# comparator-denary-buffer.net
KiCad netlist of a schematic drawn in EAGLE
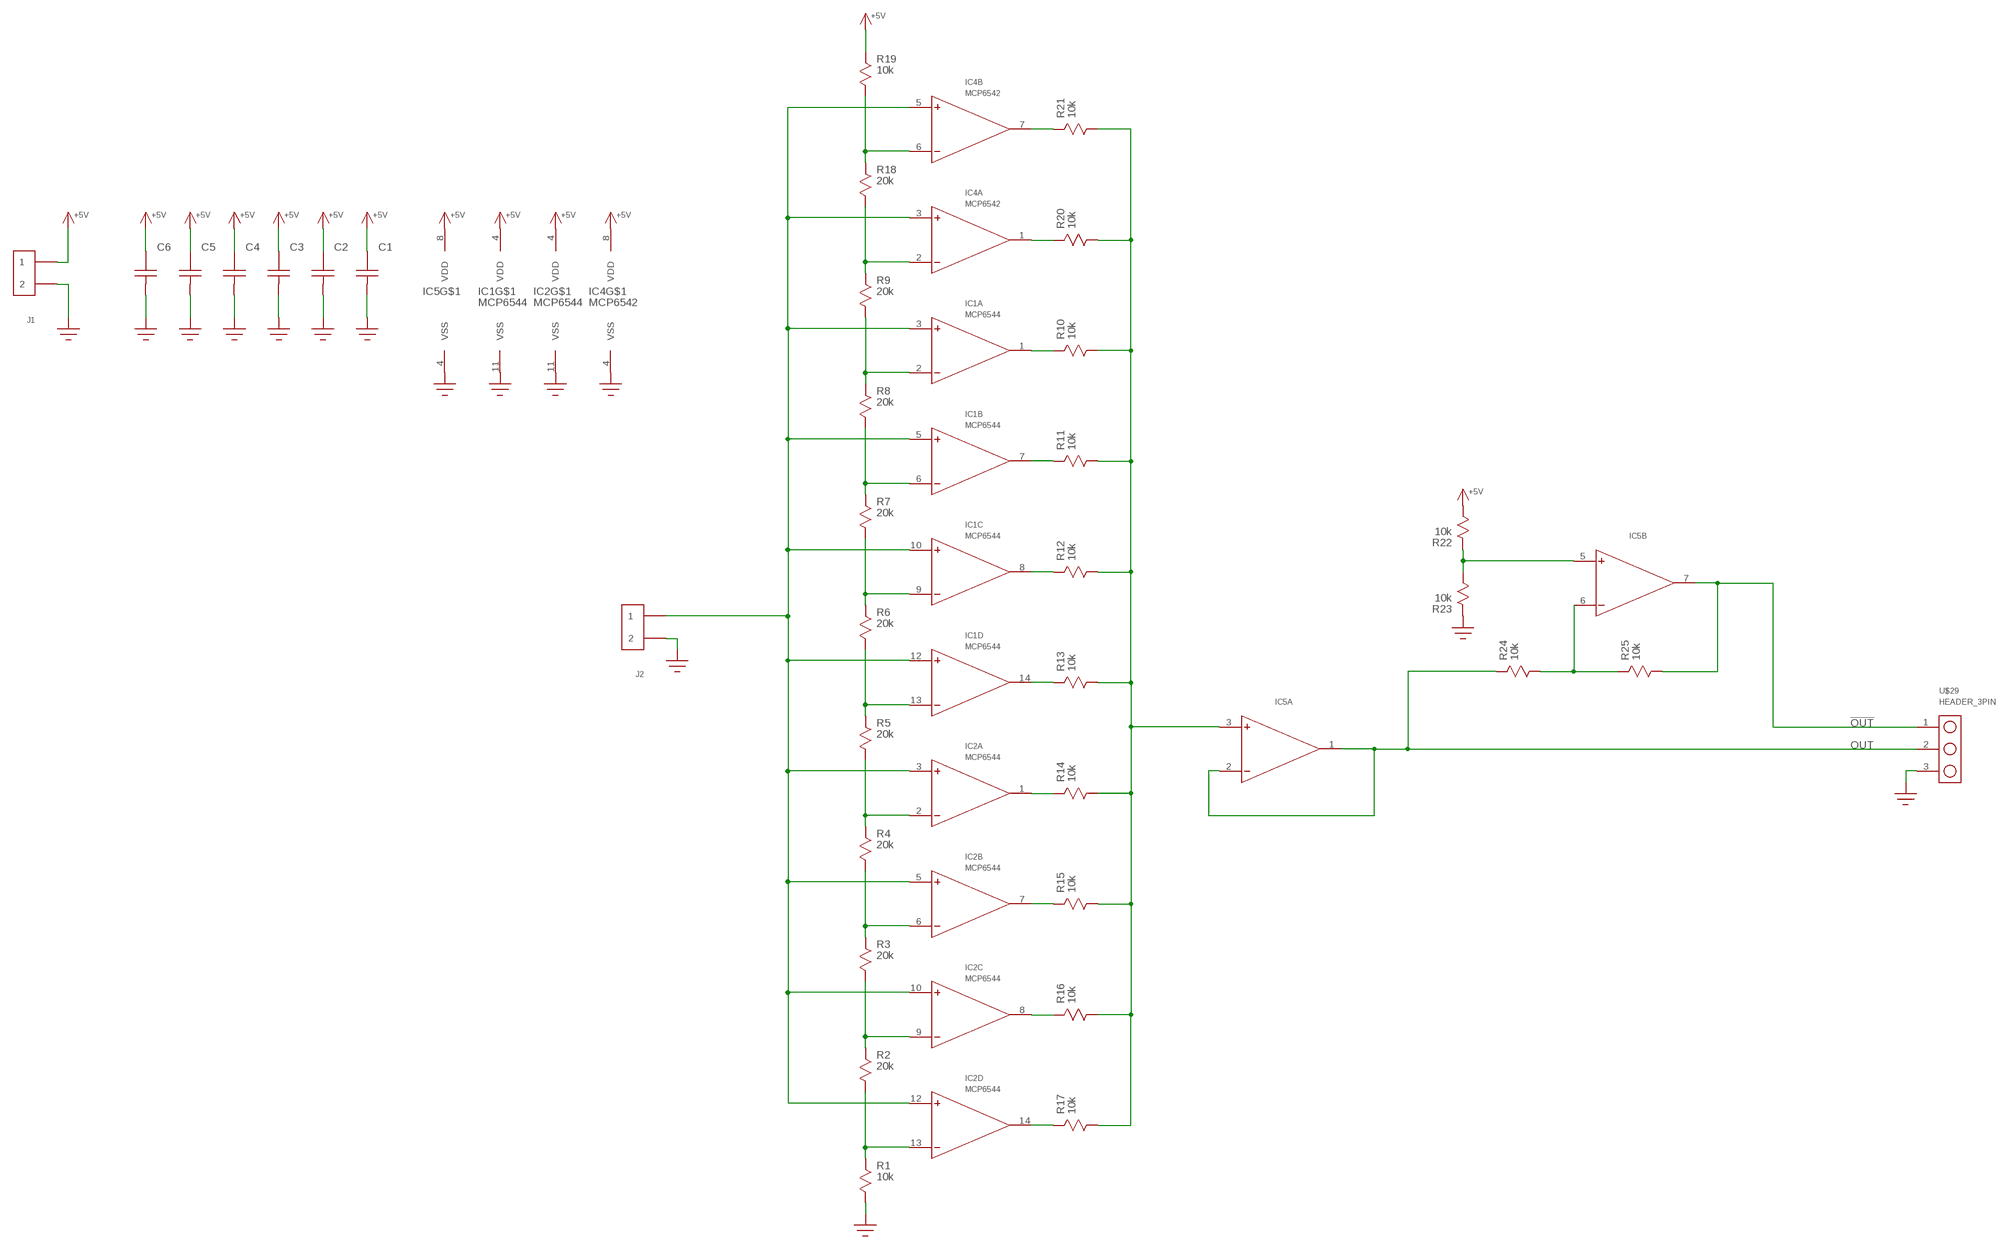
[diagram p0: schematic, sheet 1]

(export (version "E")
  (design (tool "Eeschema 10.0.6"))
  (components
    (comp (ref "C1")
      (value "C0603")
      (footprint "eagle-import:C0603")
      (libsource (lib "eagle-import") (part "C0603"))
    )
    (comp (ref "C2")
      (value "C0603")
      (footprint "eagle-import:C0603")
      (libsource (lib "eagle-import") (part "C0603"))
    )
    (comp (ref "C3")
      (value "C0603")
      (footprint "eagle-import:C0603")
      (libsource (lib "eagle-import") (part "C0603"))
    )
    (comp (ref "C4")
      (value "C0603")
      (footprint "eagle-import:C0603")
      (libsource (lib "eagle-import") (part "C0603"))
    )
    (comp (ref "C5")
      (value "C0603")
      (footprint "eagle-import:C0603")
      (libsource (lib "eagle-import") (part "C0603"))
    )
    (comp (ref "C6")
      (value "C1206")
      (footprint "eagle-import:1206")
      (libsource (lib "eagle-import") (part "C1206"))
    )
    (comp (ref "IC1")
      (value "MCP6544")
      (footprint "eagle-import:SOIC-14")
      (libsource (lib "eagle-import") (part "MCP6544SOIC"))
    )
    (comp (ref "IC2")
      (value "MCP6544")
      (footprint "eagle-import:SOIC-14")
      (libsource (lib "eagle-import") (part "MCP6544SOIC"))
    )
    (comp (ref "IC4")
      (value "MCP6542")
      (footprint "eagle-import:SOIC8")
      (libsource (lib "eagle-import") (part "MCP6542"))
    )
    (comp (ref "IC5")
      (value "MCP6L02")
      (footprint "eagle-import:SOIC8")
      (libsource (lib "eagle-import") (part "MCP6L02"))
    )
    (comp (ref "J1")
      (value "HEADER_2PIN")
      (footprint "eagle-import:HEADER_2PIN")
      (libsource (lib "eagle-import") (part "HEADER_2PIN"))
    )
    (comp (ref "J2")
      (value "HEADER_2PIN")
      (footprint "eagle-import:HEADER_2PIN")
      (libsource (lib "eagle-import") (part "HEADER_2PIN"))
    )
    (comp (ref "R1")
      (value "10k")
      (footprint "eagle-import:R0603")
      (libsource (lib "eagle-import") (part "R0603"))
    )
    (comp (ref "R2")
      (value "20k")
      (footprint "eagle-import:R0603")
      (libsource (lib "eagle-import") (part "R0603"))
    )
    (comp (ref "R3")
      (value "20k")
      (footprint "eagle-import:R0603")
      (libsource (lib "eagle-import") (part "R0603"))
    )
    (comp (ref "R4")
      (value "20k")
      (footprint "eagle-import:R0603")
      (libsource (lib "eagle-import") (part "R0603"))
    )
    (comp (ref "R5")
      (value "20k")
      (footprint "eagle-import:R0603")
      (libsource (lib "eagle-import") (part "R0603"))
    )
    (comp (ref "R6")
      (value "20k")
      (footprint "eagle-import:R0603")
      (libsource (lib "eagle-import") (part "R0603"))
    )
    (comp (ref "R7")
      (value "20k")
      (footprint "eagle-import:R0603")
      (libsource (lib "eagle-import") (part "R0603"))
    )
    (comp (ref "R8")
      (value "20k")
      (footprint "eagle-import:R0603")
      (libsource (lib "eagle-import") (part "R0603"))
    )
    (comp (ref "R9")
      (value "20k")
      (footprint "eagle-import:R0603")
      (libsource (lib "eagle-import") (part "R0603"))
    )
    (comp (ref "R10")
      (value "10k")
      (footprint "eagle-import:R0603")
      (libsource (lib "eagle-import") (part "R0603"))
    )
    (comp (ref "R11")
      (value "10k")
      (footprint "eagle-import:R0603")
      (libsource (lib "eagle-import") (part "R0603"))
    )
    (comp (ref "R12")
      (value "10k")
      (footprint "eagle-import:R0603")
      (libsource (lib "eagle-import") (part "R0603"))
    )
    (comp (ref "R13")
      (value "10k")
      (footprint "eagle-import:R0603")
      (libsource (lib "eagle-import") (part "R0603"))
    )
    (comp (ref "R14")
      (value "10k")
      (footprint "eagle-import:R0603")
      (libsource (lib "eagle-import") (part "R0603"))
    )
    (comp (ref "R15")
      (value "10k")
      (footprint "eagle-import:R0603")
      (libsource (lib "eagle-import") (part "R0603"))
    )
    (comp (ref "R16")
      (value "10k")
      (footprint "eagle-import:R0603")
      (libsource (lib "eagle-import") (part "R0603"))
    )
    (comp (ref "R17")
      (value "10k")
      (footprint "eagle-import:R0603")
      (libsource (lib "eagle-import") (part "R0603"))
    )
    (comp (ref "R18")
      (value "20k")
      (footprint "eagle-import:R0603")
      (libsource (lib "eagle-import") (part "R0603"))
    )
    (comp (ref "R19")
      (value "10k")
      (footprint "eagle-import:R0603")
      (libsource (lib "eagle-import") (part "R0603"))
    )
    (comp (ref "R20")
      (value "10k")
      (footprint "eagle-import:R0603")
      (libsource (lib "eagle-import") (part "R0603"))
    )
    (comp (ref "R21")
      (value "10k")
      (footprint "eagle-import:R0603")
      (libsource (lib "eagle-import") (part "R0603"))
    )
    (comp (ref "R22")
      (value "10k")
      (footprint "eagle-import:R0603")
      (libsource (lib "eagle-import") (part "R0603"))
    )
    (comp (ref "R23")
      (value "10k")
      (footprint "eagle-import:R0603")
      (libsource (lib "eagle-import") (part "R0603"))
    )
    (comp (ref "R24")
      (value "10k")
      (footprint "eagle-import:R0603")
      (libsource (lib "eagle-import") (part "R0603"))
    )
    (comp (ref "R25")
      (value "10k")
      (footprint "eagle-import:R0603")
      (libsource (lib "eagle-import") (part "R0603"))
    )
    (comp (ref "U$29")
      (value "HEADER_3PIN")
      (footprint "eagle-import:HEADER_3PIN")
      (libsource (lib "eagle-import") (part "HEADER_3PIN"))
    )
  )
  (nets
    (net (code "1") (name "+5V") (class "Default")
      (node (ref "C1") (pin "P$2") (pinfunction "P$2_P$2") (pintype "bidirectional"))
      (node (ref "C2") (pin "P$2") (pinfunction "P$2_P$2") (pintype "bidirectional"))
      (node (ref "C3") (pin "P$2") (pinfunction "P$2_P$2") (pintype "bidirectional"))
      (node (ref "C4") (pin "P$2") (pinfunction "P$2_P$2") (pintype "bidirectional"))
      (node (ref "C5") (pin "P$2") (pinfunction "P$2_P$2") (pintype "bidirectional"))
      (node (ref "C6") (pin "P$2") (pinfunction "P$2_P$2") (pintype "bidirectional"))
      (node (ref "IC1") (pin "4") (pinfunction "VDD_4") (pintype "bidirectional"))
      (node (ref "IC2") (pin "4") (pinfunction "VDD_4") (pintype "bidirectional"))
      (node (ref "IC4") (pin "8") (pinfunction "VDD_8") (pintype "bidirectional"))
      (node (ref "IC5") (pin "8") (pinfunction "VDD_8") (pintype "bidirectional"))
      (node (ref "J1") (pin "1") (pinfunction "1_1") (pintype "bidirectional"))
      (node (ref "R19") (pin "P$1") (pinfunction "P$3_P$1") (pintype "bidirectional"))
      (node (ref "R22") (pin "P$2") (pinfunction "P$4_P$2") (pintype "bidirectional"))
    )
    (net (code "2") (name "/OUT") (class "Default")
      (node (ref "IC5") (pin "1") (pinfunction "OUT_1") (pintype "bidirectional"))
      (node (ref "IC5") (pin "2") (pinfunction "-_2") (pintype "bidirectional"))
      (node (ref "R24") (pin "P$1") (pinfunction "P$3_P$1") (pintype "bidirectional"))
      (node (ref "U$29") (pin "2") (pinfunction "2_2") (pintype "bidirectional"))
    )
    (net (code "3") (name "/~{OUT}") (class "Default")
      (node (ref "IC5") (pin "7") (pinfunction "OUT_7") (pintype "bidirectional"))
      (node (ref "R25") (pin "P$2") (pinfunction "P$4_P$2") (pintype "bidirectional"))
      (node (ref "U$29") (pin "1") (pinfunction "1_1") (pintype "bidirectional"))
    )
    (net (code "4") (name "GND") (class "Default")
      (node (ref "C1") (pin "P$1") (pinfunction "P$1_P$1") (pintype "bidirectional"))
      (node (ref "C2") (pin "P$1") (pinfunction "P$1_P$1") (pintype "bidirectional"))
      (node (ref "C3") (pin "P$1") (pinfunction "P$1_P$1") (pintype "bidirectional"))
      (node (ref "C4") (pin "P$1") (pinfunction "P$1_P$1") (pintype "bidirectional"))
      (node (ref "C5") (pin "P$1") (pinfunction "P$1_P$1") (pintype "bidirectional"))
      (node (ref "C6") (pin "P$1") (pinfunction "P$1_P$1") (pintype "bidirectional"))
      (node (ref "IC1") (pin "11") (pinfunction "VSS_11") (pintype "bidirectional"))
      (node (ref "IC2") (pin "11") (pinfunction "VSS_11") (pintype "bidirectional"))
      (node (ref "IC4") (pin "4") (pinfunction "VSS_4") (pintype "bidirectional"))
      (node (ref "IC5") (pin "4") (pinfunction "VSS_4") (pintype "bidirectional"))
      (node (ref "J1") (pin "2") (pinfunction "2_2") (pintype "bidirectional"))
      (node (ref "J2") (pin "2") (pinfunction "2_2") (pintype "bidirectional"))
      (node (ref "R1") (pin "P$2") (pinfunction "P$4_P$2") (pintype "bidirectional"))
      (node (ref "R23") (pin "P$1") (pinfunction "P$3_P$1") (pintype "bidirectional"))
      (node (ref "U$29") (pin "3") (pinfunction "3_3") (pintype "bidirectional"))
    )
    (net (code "5") (name "Net-(IC1A-+)") (class "Default")
      (node (ref "IC1") (pin "10") (pinfunction "+_10") (pintype "bidirectional"))
      (node (ref "IC1") (pin "12") (pinfunction "+_12") (pintype "bidirectional"))
      (node (ref "IC1") (pin "3") (pinfunction "+_3") (pintype "bidirectional"))
      (node (ref "IC1") (pin "5") (pinfunction "+_5") (pintype "bidirectional"))
      (node (ref "IC2") (pin "10") (pinfunction "+_10") (pintype "bidirectional"))
      (node (ref "IC2") (pin "12") (pinfunction "+_12") (pintype "bidirectional"))
      (node (ref "IC2") (pin "3") (pinfunction "+_3") (pintype "bidirectional"))
      (node (ref "IC2") (pin "5") (pinfunction "+_5") (pintype "bidirectional"))
      (node (ref "IC4") (pin "3") (pinfunction "+_3") (pintype "bidirectional"))
      (node (ref "IC4") (pin "5") (pinfunction "+_5") (pintype "bidirectional"))
      (node (ref "J2") (pin "1") (pinfunction "1_1") (pintype "bidirectional"))
    )
    (net (code "6") (name "Net-(IC1A--)") (class "Default")
      (node (ref "IC1") (pin "2") (pinfunction "-_2") (pintype "bidirectional"))
      (node (ref "R8") (pin "P$1") (pinfunction "P$3_P$1") (pintype "bidirectional"))
      (node (ref "R9") (pin "P$2") (pinfunction "P$4_P$2") (pintype "bidirectional"))
    )
    (net (code "7") (name "Net-(IC1A-OUT)") (class "Default")
      (node (ref "IC1") (pin "1") (pinfunction "OUT_1") (pintype "bidirectional"))
      (node (ref "R10") (pin "P$1") (pinfunction "P$3_P$1") (pintype "bidirectional"))
    )
    (net (code "8") (name "Net-(IC1B--)") (class "Default")
      (node (ref "IC1") (pin "6") (pinfunction "-_6") (pintype "bidirectional"))
      (node (ref "R7") (pin "P$1") (pinfunction "P$3_P$1") (pintype "bidirectional"))
      (node (ref "R8") (pin "P$2") (pinfunction "P$4_P$2") (pintype "bidirectional"))
    )
    (net (code "9") (name "Net-(IC1B-OUT)") (class "Default")
      (node (ref "IC1") (pin "7") (pinfunction "OUT_7") (pintype "bidirectional"))
      (node (ref "R11") (pin "P$1") (pinfunction "P$3_P$1") (pintype "bidirectional"))
    )
    (net (code "10") (name "Net-(IC1C--)") (class "Default")
      (node (ref "IC1") (pin "9") (pinfunction "-_9") (pintype "bidirectional"))
      (node (ref "R6") (pin "P$1") (pinfunction "P$3_P$1") (pintype "bidirectional"))
      (node (ref "R7") (pin "P$2") (pinfunction "P$4_P$2") (pintype "bidirectional"))
    )
    (net (code "11") (name "Net-(IC1C-OUT)") (class "Default")
      (node (ref "IC1") (pin "8") (pinfunction "OUT_8") (pintype "bidirectional"))
      (node (ref "R12") (pin "P$1") (pinfunction "P$3_P$1") (pintype "bidirectional"))
    )
    (net (code "12") (name "Net-(IC1D--)") (class "Default")
      (node (ref "IC1") (pin "13") (pinfunction "-_13") (pintype "bidirectional"))
      (node (ref "R5") (pin "P$1") (pinfunction "P$3_P$1") (pintype "bidirectional"))
      (node (ref "R6") (pin "P$2") (pinfunction "P$4_P$2") (pintype "bidirectional"))
    )
    (net (code "13") (name "Net-(IC1D-OUT)") (class "Default")
      (node (ref "IC1") (pin "14") (pinfunction "OUT_14") (pintype "bidirectional"))
      (node (ref "R13") (pin "P$1") (pinfunction "P$3_P$1") (pintype "bidirectional"))
    )
    (net (code "14") (name "Net-(IC2A--)") (class "Default")
      (node (ref "IC2") (pin "2") (pinfunction "-_2") (pintype "bidirectional"))
      (node (ref "R4") (pin "P$1") (pinfunction "P$3_P$1") (pintype "bidirectional"))
      (node (ref "R5") (pin "P$2") (pinfunction "P$4_P$2") (pintype "bidirectional"))
    )
    (net (code "15") (name "Net-(IC2A-OUT)") (class "Default")
      (node (ref "IC2") (pin "1") (pinfunction "OUT_1") (pintype "bidirectional"))
      (node (ref "R14") (pin "P$1") (pinfunction "P$3_P$1") (pintype "bidirectional"))
    )
    (net (code "16") (name "Net-(IC2B--)") (class "Default")
      (node (ref "IC2") (pin "6") (pinfunction "-_6") (pintype "bidirectional"))
      (node (ref "R3") (pin "P$1") (pinfunction "P$3_P$1") (pintype "bidirectional"))
      (node (ref "R4") (pin "P$2") (pinfunction "P$4_P$2") (pintype "bidirectional"))
    )
    (net (code "17") (name "Net-(IC2B-OUT)") (class "Default")
      (node (ref "IC2") (pin "7") (pinfunction "OUT_7") (pintype "bidirectional"))
      (node (ref "R15") (pin "P$1") (pinfunction "P$3_P$1") (pintype "bidirectional"))
    )
    (net (code "18") (name "Net-(IC2C--)") (class "Default")
      (node (ref "IC2") (pin "9") (pinfunction "-_9") (pintype "bidirectional"))
      (node (ref "R2") (pin "P$1") (pinfunction "P$3_P$1") (pintype "bidirectional"))
      (node (ref "R3") (pin "P$2") (pinfunction "P$4_P$2") (pintype "bidirectional"))
    )
    (net (code "19") (name "Net-(IC2C-OUT)") (class "Default")
      (node (ref "IC2") (pin "8") (pinfunction "OUT_8") (pintype "bidirectional"))
      (node (ref "R16") (pin "P$1") (pinfunction "P$3_P$1") (pintype "bidirectional"))
    )
    (net (code "20") (name "Net-(IC2D--)") (class "Default")
      (node (ref "IC2") (pin "13") (pinfunction "-_13") (pintype "bidirectional"))
      (node (ref "R1") (pin "P$1") (pinfunction "P$3_P$1") (pintype "bidirectional"))
      (node (ref "R2") (pin "P$2") (pinfunction "P$4_P$2") (pintype "bidirectional"))
    )
    (net (code "21") (name "Net-(IC2D-OUT)") (class "Default")
      (node (ref "IC2") (pin "14") (pinfunction "OUT_14") (pintype "bidirectional"))
      (node (ref "R17") (pin "P$1") (pinfunction "P$3_P$1") (pintype "bidirectional"))
    )
    (net (code "22") (name "Net-(IC4A--)") (class "Default")
      (node (ref "IC4") (pin "2") (pinfunction "-_2") (pintype "bidirectional"))
      (node (ref "R18") (pin "P$2") (pinfunction "P$4_P$2") (pintype "bidirectional"))
      (node (ref "R9") (pin "P$1") (pinfunction "P$3_P$1") (pintype "bidirectional"))
    )
    (net (code "23") (name "Net-(IC4A-OUT)") (class "Default")
      (node (ref "IC4") (pin "1") (pinfunction "OUT_1") (pintype "bidirectional"))
      (node (ref "R20") (pin "P$1") (pinfunction "P$3_P$1") (pintype "bidirectional"))
    )
    (net (code "24") (name "Net-(IC4B--)") (class "Default")
      (node (ref "IC4") (pin "6") (pinfunction "-_6") (pintype "bidirectional"))
      (node (ref "R18") (pin "P$1") (pinfunction "P$3_P$1") (pintype "bidirectional"))
      (node (ref "R19") (pin "P$2") (pinfunction "P$4_P$2") (pintype "bidirectional"))
    )
    (net (code "25") (name "Net-(IC4B-OUT)") (class "Default")
      (node (ref "IC4") (pin "7") (pinfunction "OUT_7") (pintype "bidirectional"))
      (node (ref "R21") (pin "P$1") (pinfunction "P$3_P$1") (pintype "bidirectional"))
    )
    (net (code "26") (name "Net-(IC5A-+)") (class "Default")
      (node (ref "IC5") (pin "3") (pinfunction "+_3") (pintype "bidirectional"))
      (node (ref "R10") (pin "P$2") (pinfunction "P$4_P$2") (pintype "bidirectional"))
      (node (ref "R11") (pin "P$2") (pinfunction "P$4_P$2") (pintype "bidirectional"))
      (node (ref "R12") (pin "P$2") (pinfunction "P$4_P$2") (pintype "bidirectional"))
      (node (ref "R13") (pin "P$2") (pinfunction "P$4_P$2") (pintype "bidirectional"))
      (node (ref "R14") (pin "P$2") (pinfunction "P$4_P$2") (pintype "bidirectional"))
      (node (ref "R15") (pin "P$2") (pinfunction "P$4_P$2") (pintype "bidirectional"))
      (node (ref "R16") (pin "P$2") (pinfunction "P$4_P$2") (pintype "bidirectional"))
      (node (ref "R17") (pin "P$2") (pinfunction "P$4_P$2") (pintype "bidirectional"))
      (node (ref "R20") (pin "P$2") (pinfunction "P$4_P$2") (pintype "bidirectional"))
      (node (ref "R21") (pin "P$2") (pinfunction "P$4_P$2") (pintype "bidirectional"))
    )
    (net (code "27") (name "Net-(IC5B-+)") (class "Default")
      (node (ref "IC5") (pin "5") (pinfunction "+_5") (pintype "bidirectional"))
      (node (ref "R22") (pin "P$1") (pinfunction "P$3_P$1") (pintype "bidirectional"))
      (node (ref "R23") (pin "P$2") (pinfunction "P$4_P$2") (pintype "bidirectional"))
    )
    (net (code "28") (name "Net-(IC5B--)") (class "Default")
      (node (ref "IC5") (pin "6") (pinfunction "-_6") (pintype "bidirectional"))
      (node (ref "R24") (pin "P$2") (pinfunction "P$4_P$2") (pintype "bidirectional"))
      (node (ref "R25") (pin "P$1") (pinfunction "P$3_P$1") (pintype "bidirectional"))
    )
  )
)
